# Regulators.net
KiCad netlist of a schematic drawn in Altium Designer
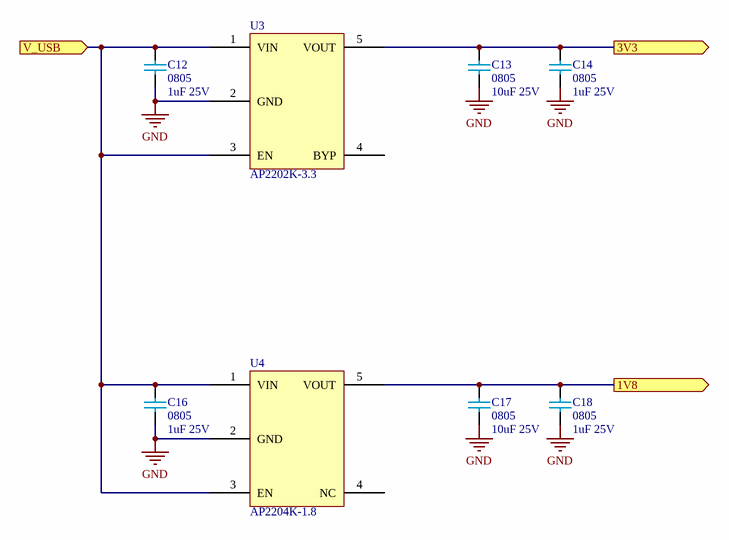
[diagram p0: Regulators.SchDoc]

(export (version "E")
  (design (tool "Eeschema 10.0.6"))
  (components
    (comp (ref "C12")
      (value "0805")
      (footprint "0805 - TALL")
      (description "0805, X5R or better")
      (fields (field (name "ALTIUM_VALUE") "1uF 25V"))
      (libsource (lib "Chip_Passives") (part "Cap 1uF 25V"))
    )
    (comp (ref "C13")
      (value "0805")
      (footprint "0805 - TALL")
      (description "0805, X5R or better")
      (fields (field (name "ALTIUM_VALUE") "10uF 25V"))
      (libsource (lib "Chip_Passives") (part "Cap 10uF 25V"))
    )
    (comp (ref "C14")
      (value "0805")
      (footprint "0805 - TALL")
      (description "0805, X5R or better")
      (fields (field (name "ALTIUM_VALUE") "1uF 25V"))
      (libsource (lib "Chip_Passives") (part "Cap 1uF 25V"))
    )
    (comp (ref "C16")
      (value "0805")
      (footprint "0805 - TALL")
      (description "0805, X5R or better")
      (fields (field (name "ALTIUM_VALUE") "1uF 25V"))
      (libsource (lib "Chip_Passives") (part "Cap 1uF 25V"))
    )
    (comp (ref "C17")
      (value "0805")
      (footprint "0805 - TALL")
      (description "0805, X5R or better")
      (fields (field (name "ALTIUM_VALUE") "10uF 25V"))
      (libsource (lib "Chip_Passives") (part "Cap 10uF 25V"))
    )
    (comp (ref "C18")
      (value "0805")
      (footprint "0805 - TALL")
      (description "0805, X5R or better")
      (fields (field (name "ALTIUM_VALUE") "1uF 25V"))
      (libsource (lib "Chip_Passives") (part "Cap 1uF 25V"))
    )
    (comp (ref "U3")
      (value "AP2202K-3.3")
      (footprint "AP2202 - SOT95P270X145-5N")
      (description "3.3V 150mA LDO regulator")
      (libsource (lib "PowerSupply") (part "AP2202K-3.3"))
    )
    (comp (ref "U4")
      (value "AP2204K-1.8")
      (footprint "AP2202 - SOT95P270X145-5N")
      (description "Linear Voltage Regulator IC 1 Output 150mA SOT-23-5")
      (libsource (lib "PowerSupply") (part "AP2204K-1.8"))
    )
  )
  (nets
    (net (code "1") (name "/1V8") (class "Default")
      (node (ref "C17") (pin "2") (pinfunction "2_2") (pintype "passive"))
      (node (ref "C18") (pin "2") (pinfunction "2_2") (pintype "passive"))
      (node (ref "U4") (pin "5") (pinfunction "VOUT_5") (pintype "passive"))
    )
    (net (code "2") (name "/3V3") (class "Default")
      (node (ref "C13") (pin "2") (pinfunction "2_2") (pintype "passive"))
      (node (ref "C14") (pin "2") (pinfunction "2_2") (pintype "passive"))
      (node (ref "U3") (pin "5") (pinfunction "VOUT_5") (pintype "passive"))
    )
    (net (code "3") (name "/V_USB") (class "Default")
      (node (ref "C12") (pin "2") (pinfunction "2_2") (pintype "passive"))
      (node (ref "C16") (pin "2") (pinfunction "2_2") (pintype "passive"))
      (node (ref "U3") (pin "1") (pinfunction "VIN_1") (pintype "passive"))
      (node (ref "U3") (pin "3") (pinfunction "EN_3") (pintype "passive"))
      (node (ref "U4") (pin "1") (pinfunction "VIN_1") (pintype "passive"))
      (node (ref "U4") (pin "3") (pinfunction "EN_3") (pintype "passive"))
    )
    (net (code "4") (name "GND") (class "Default")
      (node (ref "C12") (pin "1") (pinfunction "1_1") (pintype "passive"))
      (node (ref "C13") (pin "1") (pinfunction "1_1") (pintype "passive"))
      (node (ref "C14") (pin "1") (pinfunction "1_1") (pintype "passive"))
      (node (ref "C16") (pin "1") (pinfunction "1_1") (pintype "passive"))
      (node (ref "C17") (pin "1") (pinfunction "1_1") (pintype "passive"))
      (node (ref "C18") (pin "1") (pinfunction "1_1") (pintype "passive"))
      (node (ref "U3") (pin "2") (pinfunction "GND_2") (pintype "passive"))
      (node (ref "U4") (pin "2") (pinfunction "GND_2") (pintype "passive"))
    )
    (net (code "5") (name "unconnected-(U3-BYP-Pad4)") (class "Default")
      (node (ref "U3") (pin "4") (pinfunction "BYP_4") (pintype "passive"))
    )
    (net (code "6") (name "unconnected-(U4-NC-Pad4)") (class "Default")
      (node (ref "U4") (pin "4") (pinfunction "NC_4") (pintype "passive"))
    )
  )
)
